# Top.net
KiCad netlist of a schematic drawn in Altium Designer
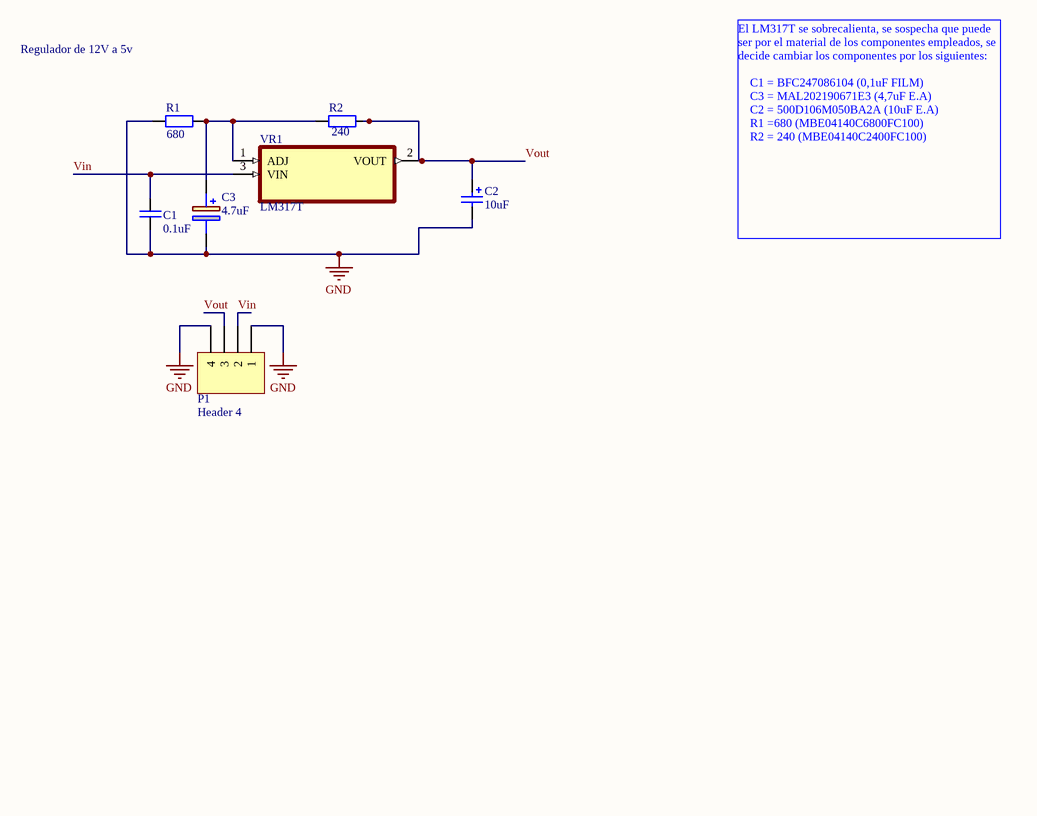
[diagram p0: Top.SchDoc]

(export (version "E")
  (design (tool "Eeschema 10.0.6"))
  (components
    (comp (ref "C1")
      (value "0.1uF")
      (footprint "CAP_RADIAL_5mm")
      (description "Condensadores de película .1uF 5% 100volts")
      (fields (field (name "MF") "Vishay") (field (name "MP") "CRCW06034K70FKEA"))
      (libsource (lib "INSU") (part "BFC247086104"))
    )
    (comp (ref "C2")
      (value "10uF")
      (footprint "POLAR0.8")
      (description "Polarized Capacitor (Axial)")
      (fields (field (name "Comment") "500D106M050BA2A") (field (name "PUBLISHER") "Altium Limited"))
      (libsource (lib "Miscellaneous Devices") (part "Cap Pol2"))
    )
    (comp (ref "C3")
      (value "4.7uF")
      (footprint "CAP_AXIAL")
      (description "Condensadores electrolíticos de aluminio (con terminales axiales) 4.7uF 63V 20%")
      (fields
        (field (name "MOUSER PART NUMBER") "594-MAL214699104E3")
        (field (name "MANUFACTURER_PART_NUMBER") "MAL214699104E3")
      )
      (libsource (lib "INSU") (part "MAL202190671E3"))
    )
    (comp (ref "P1")
      (value "Header 4")
      (footprint "HDR1X4")
      (description "Header, 4-Pin")
      (fields (field (name "PUBLISHER") "Altium Limited"))
      (libsource (lib "Miscellaneous Connectors") (part "Header 4"))
    )
    (comp (ref "R1")
      (value "680")
      (footprint "AXIAL-0.4")
      (description "Resistor")
      (fields (field (name "Comment") "MBE04140C6800FC100") (field (name "PUBLISHER") "Altium Limited"))
      (libsource (lib "Miscellaneous Devices") (part "Res2"))
    )
    (comp (ref "R2")
      (value "240")
      (footprint "AXIAL-0.4")
      (description "Resistor")
      (fields (field (name "Comment") "MBE04140C2400FC100") (field (name "PUBLISHER") "Altium Limited"))
      (libsource (lib "Miscellaneous Devices") (part "Res2"))
    )
    (comp (ref "VR1")
      (value "LM317T")
      (footprint "TO254P1054X470X1955-3")
      (description "1.5-A, 40-V, adjustable linear voltage regulator 3-TO-220")
      (fields (field (name "MF") "Texas Instruments"))
      (libsource (lib "INSU") (part "LM317T"))
    )
  )
  (nets
    (net (code "1") (name "/Vin") (class "Default")
      (node (ref "C1") (pin "1") (pinfunction "1_1") (pintype "passive"))
      (node (ref "P1") (pin "2") (pinfunction "2_2") (pintype "passive"))
      (node (ref "VR1") (pin "3") (pinfunction "VIN_3") (pintype "input"))
    )
    (net (code "2") (name "/Vout") (class "Default")
      (node (ref "C2") (pin "1") (pinfunction "1_1") (pintype "passive"))
      (node (ref "P1") (pin "3") (pinfunction "3_3") (pintype "passive"))
      (node (ref "R2") (pin "2") (pinfunction "2_2") (pintype "passive"))
      (node (ref "VR1") (pin "2") (pinfunction "VOUT_2") (pintype "output"))
    )
    (net (code "3") (name "GND") (class "Default")
      (node (ref "C1") (pin "2") (pinfunction "2_2") (pintype "passive"))
      (node (ref "C2") (pin "2") (pinfunction "2_2") (pintype "passive"))
      (node (ref "C3") (pin "2") (pinfunction "-_2") (pintype "passive"))
      (node (ref "P1") (pin "1") (pinfunction "1_1") (pintype "passive"))
      (node (ref "P1") (pin "4") (pinfunction "4_4") (pintype "passive"))
      (node (ref "R1") (pin "1") (pinfunction "1_1") (pintype "passive"))
    )
    (net (code "4") (name "Net-(C3-+)") (class "Default")
      (node (ref "C3") (pin "1") (pinfunction "+_1") (pintype "passive"))
      (node (ref "R1") (pin "2") (pinfunction "2_2") (pintype "passive"))
      (node (ref "R2") (pin "1") (pinfunction "1_1") (pintype "passive"))
      (node (ref "VR1") (pin "1") (pinfunction "ADJ_1") (pintype "input"))
    )
  )
)
